# LoPoSwitchWiFi_v2_1.net
KiCad netlist of a schematic drawn in EasyEDA
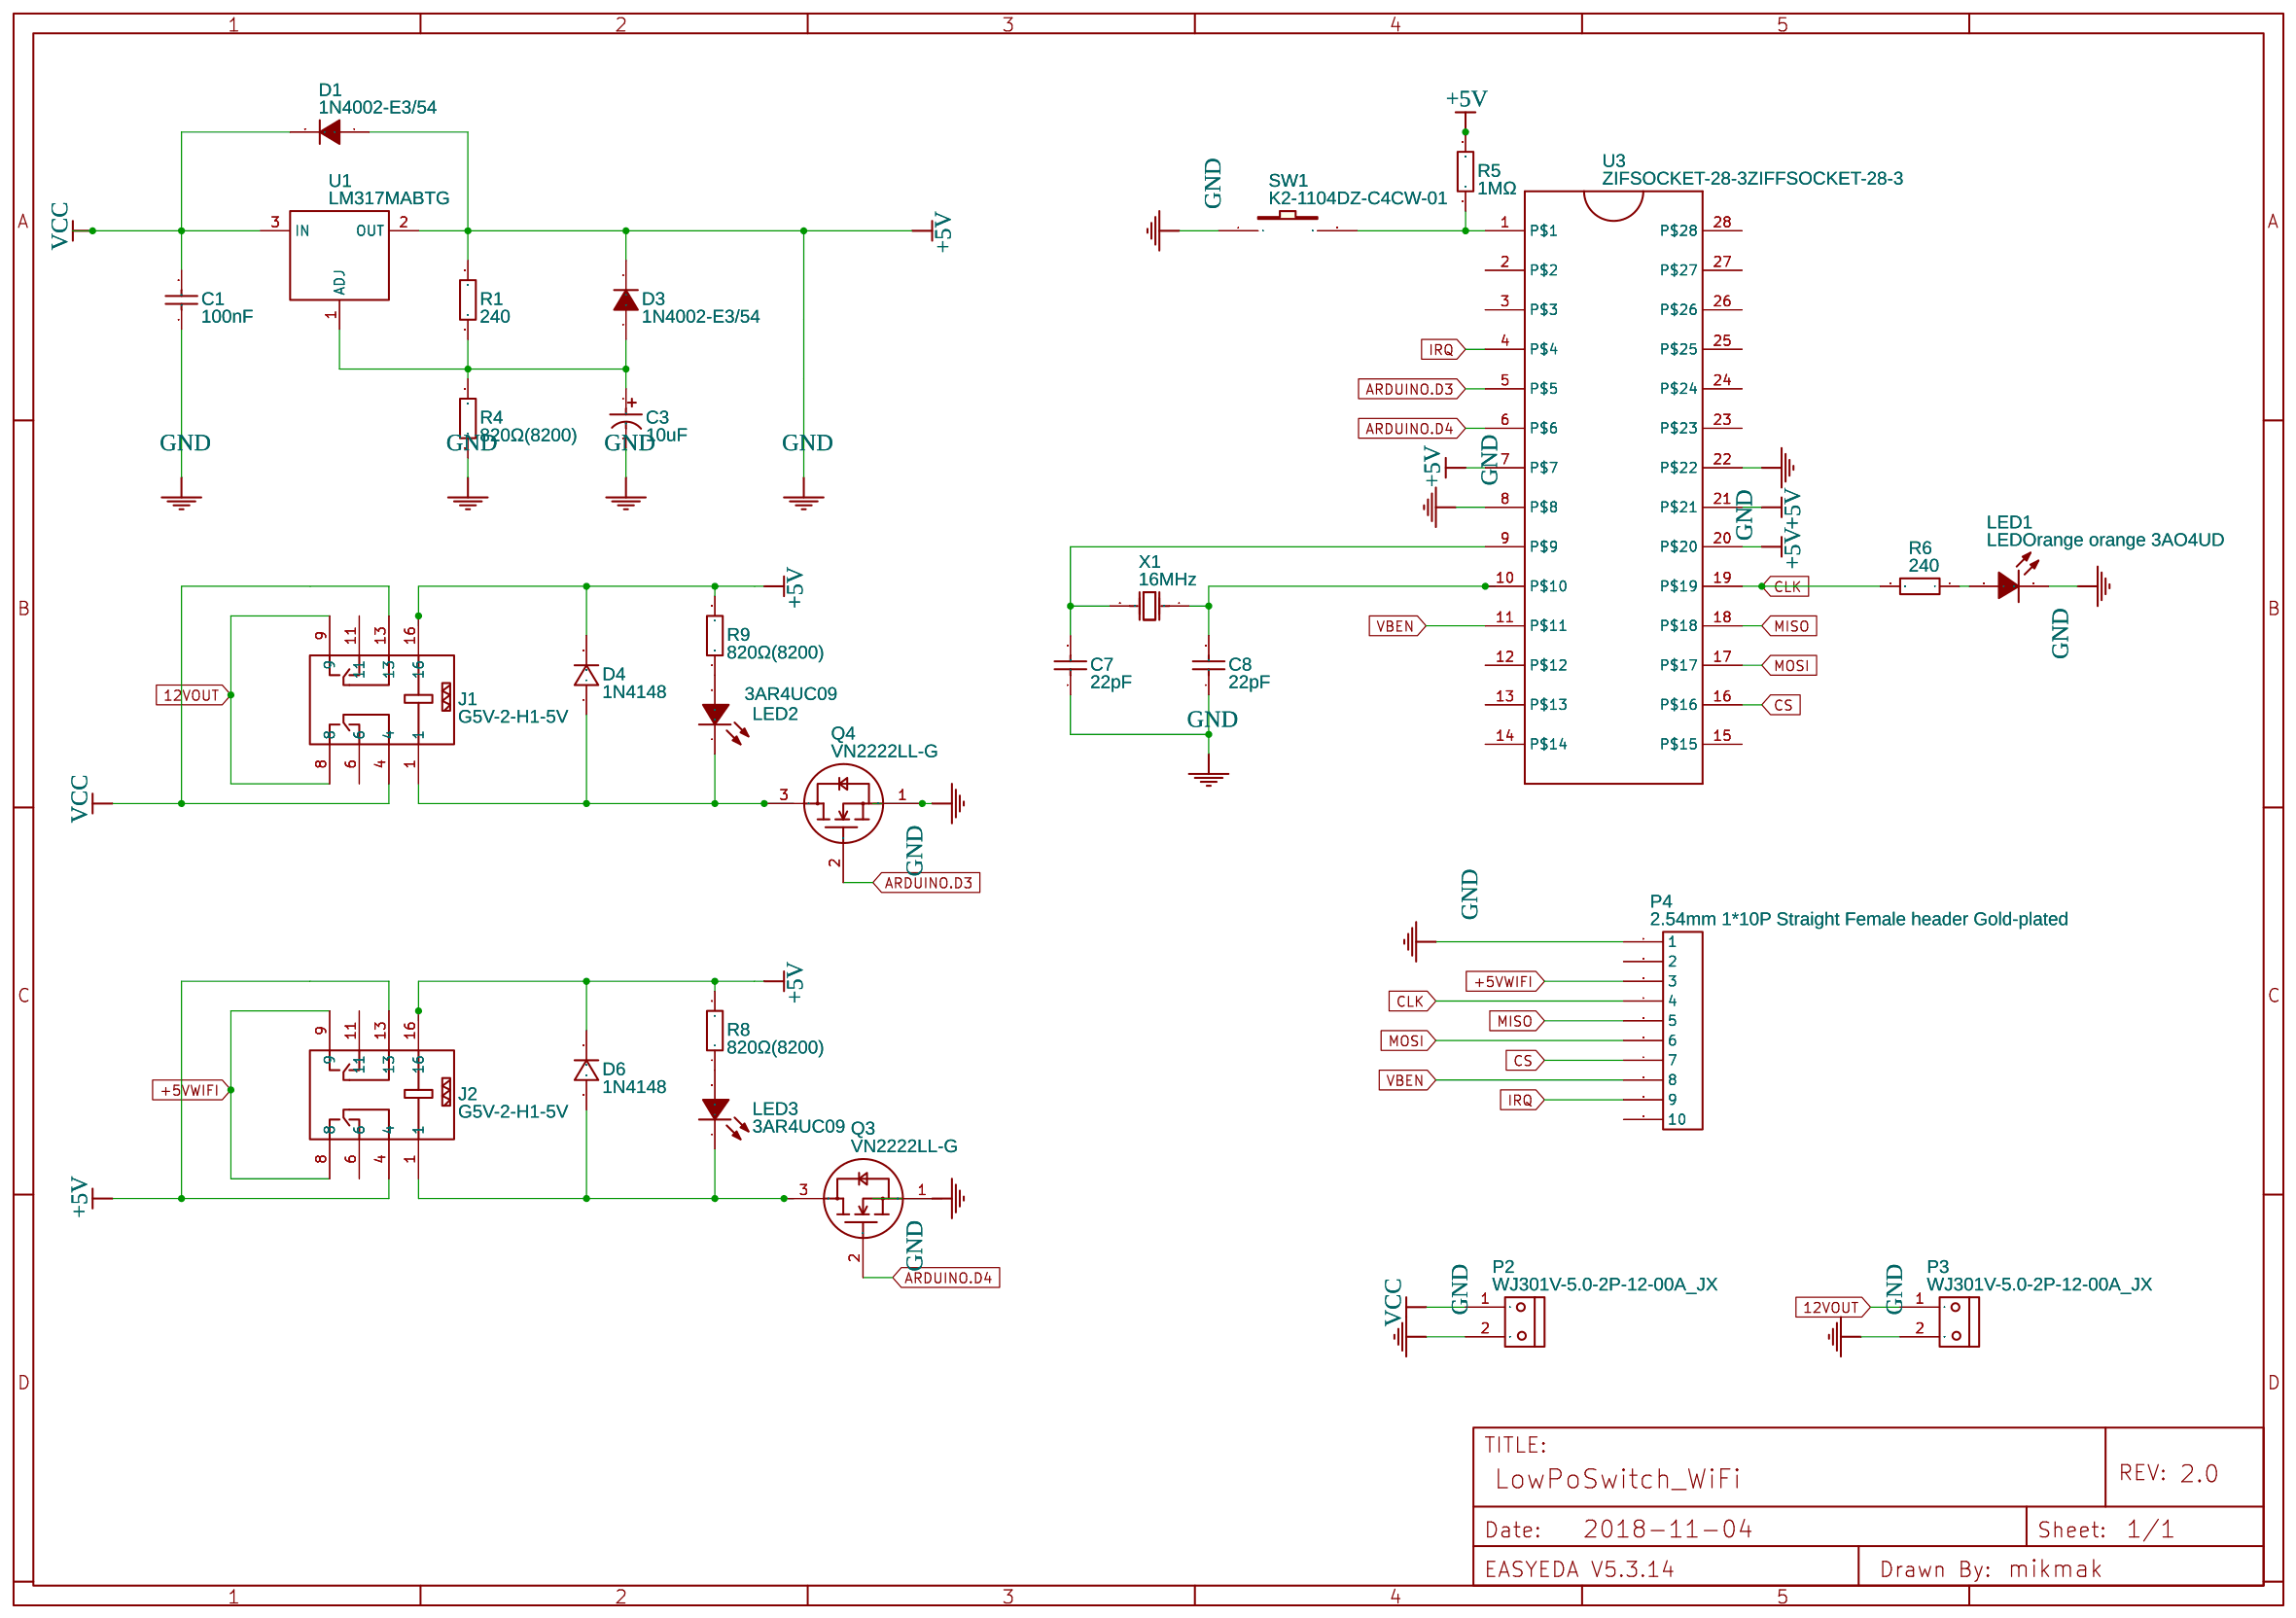
[diagram p0: schematic sheet]

(export (version "E")
  (design (tool "Eeschema 10.0.6"))
  (components
    (comp (ref "C1")
      (value "100nF")
      (fields
        (field (name "BOM_Manufacturer Part") "MPP104K5130508LC")
        (field (name "BOM_Supplier Part") "C109523")
      )
      (libsource (lib "") (part "MPP104K5130508LC"))
    )
    (comp (ref "C3")
      (value "10uF")
      (fields (field (name "BOM_Manufacturer Part") "10uf/100V") (field (name "BOM_Supplier Part") "C2029"))
      (libsource (lib "") (part "10uf/100V"))
    )
    (comp (ref "C7")
      (value "22pF")
      (fields
        (field (name "BOM_Manufacturer Part") "Monolithic0603N220J500")
        (field (name "BOM_Supplier Part") "C110283")
      )
      (libsource (lib "") (part "Monolithic0603N220J500"))
    )
    (comp (ref "C8")
      (value "22pF")
      (fields
        (field (name "BOM_Manufacturer Part") "Monolithic0603N220J500")
        (field (name "BOM_Supplier Part") "C110283")
      )
      (libsource (lib "") (part "Monolithic0603N220J500"))
    )
    (comp (ref "D1")
      (value "1N4002-E3/54")
      (fields (field (name "BOM_Supplier Part") "C33504"))
      (libsource (lib "") (part "Unknown_160_60"))
    )
    (comp (ref "D3")
      (value "1N4002-E3/54")
      (fields (field (name "BOM_Supplier Part") "C33504"))
      (libsource (lib "") (part "Unknown_310_145"))
    )
    (comp (ref "D4")
      (value "1N4148")
      (fields (field (name "BOM_Supplier Part") "C163750"))
      (libsource (lib "") (part "Unknown_290_335"))
    )
    (comp (ref "D6")
      (value "1N4148")
      (fields (field (name "BOM_Supplier Part") "C163750"))
      (libsource (lib "") (part "Unknown_290_535"))
    )
    (comp (ref "J1")
      (value "G5V-2-H1-5V")
      (fields (field (name "BOM_Supplier Part") "C28066"))
      (libsource (lib "") (part "Unknown_185_340"))
    )
    (comp (ref "J2")
      (value "G5V-2-H1-5V")
      (fields (field (name "BOM_Supplier Part") "C28066"))
      (libsource (lib "") (part "Unknown_185_540"))
    )
    (comp (ref "LED1")
      (value "LEDOrange orange 3AO4UD")
      (fields (field (name "BOM_Supplier Part") "C62095"))
      (libsource (lib "") (part "Unknown_1010_290"))
    )
    (comp (ref "LED2")
      (value "3AR4UC09")
      (fields (field (name "BOM_Supplier Part") "C6211"))
      (libsource (lib "") (part "Unknown_355_355"))
    )
    (comp (ref "LED3")
      (value "3AR4UC09")
      (fields (field (name "BOM_Supplier Part") "C6211"))
      (libsource (lib "") (part "Unknown_355_555"))
    )
    (comp (ref "P2")
      (value "WJ301V-5.0-2P-12-00A_JX")
      (fields (field (name "BOM_Manufacturer Part") "?") (field (name "BOM_Supplier Part") "C72326"))
      (libsource (lib "") (part "Unknown_755_655"))
    )
    (comp (ref "P3")
      (value "WJ301V-5.0-2P-12-00A_JX")
      (fields (field (name "BOM_Manufacturer Part") "?") (field (name "BOM_Supplier Part") "C72326"))
      (libsource (lib "") (part "Unknown_975_655"))
    )
    (comp (ref "P4")
      (value "2.54mm 1*10P Straight Female header Gold-plated")
      (fields (field (name "BOM_Supplier Part") "C35445"))
      (libsource (lib "") (part "Unknown_825_510"))
    )
    (comp (ref "Q3")
      (value "VN2222LL-G")
      (fields (field (name "BOM_Supplier Part") "C152170"))
      (libsource (lib "") (part "Unknown_430_610"))
    )
    (comp (ref "Q4")
      (value "VN2222LL-G")
      (fields (field (name "BOM_Supplier Part") "C152170"))
      (libsource (lib "") (part "Unknown_420_410"))
    )
    (comp (ref "R1")
      (value "240")
      (fields
        (field (name "BOM_Manufacturer Part") "MF1/8W-240Ω±1% T52")
        (field (name "BOM_Supplier Part") "C119165")
      )
      (libsource (lib "") (part "MF1/8W-240Ω±1% T52_1"))
    )
    (comp (ref "R4")
      (value "820Ω(8200)")
      (fields
        (field (name "BOM_Manufacturer Part") "MF1/8W-820Ω±1% T52")
        (field (name "BOM_Supplier Part") "C119177")
      )
      (libsource (lib "") (part "MF1/8W-820Ω±1% T52"))
    )
    (comp (ref "R5")
      (value "1MΩ")
      (fields
        (field (name "BOM_Manufacturer Part") "MFR0W4F1004A50")
        (field (name "BOM_Supplier Part") "C58596")
      )
      (libsource (lib "") (part "MFR0W4F1004A50"))
    )
    (comp (ref "R6")
      (value "240")
      (fields
        (field (name "BOM_Manufacturer Part") "MF1/8W-240Ω±1% T52")
        (field (name "BOM_Supplier Part") "C119165")
      )
      (libsource (lib "") (part "MF1/8W-240Ω±1% T52"))
    )
    (comp (ref "R8")
      (value "820Ω(8200)")
      (fields
        (field (name "BOM_Manufacturer Part") "MF1/8W-820Ω±1% T52")
        (field (name "BOM_Supplier Part") "C119177")
      )
      (libsource (lib "") (part "MF1/8W-820Ω±1% T52"))
    )
    (comp (ref "R9")
      (value "820Ω(8200)")
      (fields
        (field (name "BOM_Manufacturer Part") "MF1/8W-820Ω±1% T52")
        (field (name "BOM_Supplier Part") "C119177")
      )
      (libsource (lib "") (part "MF1/8W-820Ω±1% T52"))
    )
    (comp (ref "SW1")
      (value "K2-1104DZ-C4CW-01")
      (fields (field (name "BOM_Supplier Part") "C145889"))
      (libsource (lib "") (part "Unknown_640_110"))
    )
    (comp (ref "U1")
      (value "LM317MABTG")
      (fields (field (name "BOM_Supplier Part") "C94823"))
      (libsource (lib "") (part "Unknown_165_120"))
    )
    (comp (ref "U3")
      (value "ZIFSOCKET-28-3ZIFFSOCKET-28-3")
      (fields (field (name "BOM_Manufacturer Part") "?"))
      (libsource (lib "") (part "Unknown_765_390"))
    )
    (comp (ref "X1")
      (value "16MHz")
      (fields
        (field (name "BOM_Manufacturer Part") "X49SD16MSD2SC")
        (field (name "BOM_Supplier Part") "C16212")
      )
      (libsource (lib "") (part "X49SD16MSD2SC"))
    )
  )
  (nets
    (net (code "1") (name "+5V") (class "Default")
      (node (ref "C1") (pin "1") (pinfunction "1_1") (pintype "input"))
      (node (ref "C3") (pin "2") (pinfunction "2_2") (pintype "input"))
      (node (ref "C7") (pin "1") (pinfunction "1_1") (pintype "input"))
      (node (ref "C8") (pin "1") (pinfunction "1_1") (pintype "input"))
      (node (ref "D1") (pin "1") (pinfunction "A_1") (pintype "unspecified"))
      (node (ref "D3") (pin "2") (pinfunction "K_2") (pintype "unspecified"))
      (node (ref "D4") (pin "2") (pinfunction "2_2") (pintype "unspecified"))
      (node (ref "D6") (pin "2") (pinfunction "2_2") (pintype "unspecified"))
      (node (ref "J1") (pin "16") (pinfunction "16_16") (pintype "unspecified"))
      (node (ref "J2") (pin "13") (pinfunction "13_13") (pintype "unspecified"))
      (node (ref "J2") (pin "16") (pinfunction "16_16") (pintype "unspecified"))
      (node (ref "J2") (pin "4") (pinfunction "4_4") (pintype "unspecified"))
      (node (ref "LED1") (pin "1") (pinfunction "K_1") (pintype "unspecified"))
      (node (ref "P2") (pin "2") (pinfunction "2_2") (pintype "unspecified"))
      (node (ref "P3") (pin "2") (pinfunction "2_2") (pintype "unspecified"))
      (node (ref "P4") (pin "1") (pinfunction "1_1") (pintype "input"))
      (node (ref "Q4") (pin "1") (pinfunction "S_1") (pintype "unspecified"))
      (node (ref "R1") (pin "2") (pinfunction "2_2") (pintype "input"))
      (node (ref "R4") (pin "1") (pinfunction "1_1") (pintype "input"))
      (node (ref "R5") (pin "2") (pinfunction "2_2") (pintype "input"))
      (node (ref "R8") (pin "2") (pinfunction "2_2") (pintype "input"))
      (node (ref "R9") (pin "2") (pinfunction "2_2") (pintype "input"))
      (node (ref "SW1") (pin "1") (pinfunction "1_1") (pintype "input"))
      (node (ref "U1") (pin "2") (pinfunction "OUT_2") (pintype "unspecified"))
      (node (ref "U3") (pin "20") (pinfunction "P$20_20") (pintype "unspecified"))
      (node (ref "U3") (pin "21") (pinfunction "P$21_21") (pintype "unspecified"))
      (node (ref "U3") (pin "22") (pinfunction "P$22_22") (pintype "unspecified"))
      (node (ref "U3") (pin "7") (pinfunction "P$7_7") (pintype "unspecified"))
      (node (ref "U3") (pin "8") (pinfunction "P$8_8") (pintype "unspecified"))
    )
    (net (code "2") (name "+5VWIFI") (class "Default")
      (node (ref "J2") (pin "8") (pinfunction "8_8") (pintype "unspecified"))
      (node (ref "J2") (pin "9") (pinfunction "9_9") (pintype "unspecified"))
      (node (ref "P4") (pin "3") (pinfunction "3_3") (pintype "input"))
    )
    (net (code "3") (name "12VOUT") (class "Default")
      (node (ref "J1") (pin "8") (pinfunction "8_8") (pintype "unspecified"))
      (node (ref "J1") (pin "9") (pinfunction "9_9") (pintype "unspecified"))
      (node (ref "P3") (pin "1") (pinfunction "1_1") (pintype "unspecified"))
    )
    (net (code "4") (name "ARDUINO.D3") (class "Default")
      (node (ref "Q4") (pin "2") (pinfunction "G_2") (pintype "unspecified"))
      (node (ref "U3") (pin "5") (pinfunction "P$5_5") (pintype "unspecified"))
    )
    (net (code "5") (name "ARDUINO.D4") (class "Default")
      (node (ref "Q3") (pin "2") (pinfunction "G_2") (pintype "unspecified"))
      (node (ref "U3") (pin "6") (pinfunction "P$6_6") (pintype "unspecified"))
    )
    (net (code "6") (name "CLK") (class "Default")
      (node (ref "P4") (pin "4") (pinfunction "4_4") (pintype "input"))
      (node (ref "R6") (pin "2") (pinfunction "2_2") (pintype "input"))
      (node (ref "U3") (pin "19") (pinfunction "P$19_19") (pintype "unspecified"))
    )
    (net (code "7") (name "CS") (class "Default")
      (node (ref "P4") (pin "7") (pinfunction "7_7") (pintype "input"))
      (node (ref "U3") (pin "16") (pinfunction "P$16_16") (pintype "unspecified"))
    )
    (net (code "8") (name "IRQ") (class "Default")
      (node (ref "P4") (pin "9") (pinfunction "9_9") (pintype "input"))
      (node (ref "U3") (pin "4") (pinfunction "P$4_4") (pintype "unspecified"))
    )
    (net (code "9") (name "MISO") (class "Default")
      (node (ref "P4") (pin "5") (pinfunction "5_5") (pintype "input"))
      (node (ref "U3") (pin "18") (pinfunction "P$18_18") (pintype "unspecified"))
    )
    (net (code "10") (name "MOSI") (class "Default")
      (node (ref "P4") (pin "6") (pinfunction "6_6") (pintype "input"))
      (node (ref "U3") (pin "17") (pinfunction "P$17_17") (pintype "unspecified"))
    )
    (net (code "11") (name "Net-(D3-A)") (class "Default")
      (node (ref "C3") (pin "1") (pinfunction "1_1") (pintype "input"))
      (node (ref "D3") (pin "1") (pinfunction "A_1") (pintype "unspecified"))
      (node (ref "R1") (pin "1") (pinfunction "1_1") (pintype "input"))
      (node (ref "R4") (pin "2") (pinfunction "2_2") (pintype "input"))
      (node (ref "U1") (pin "1") (pinfunction "ADJ_1") (pintype "input"))
    )
    (net (code "12") (name "Net-(LED1-A)") (class "Default")
      (node (ref "LED1") (pin "2") (pinfunction "A_2") (pintype "unspecified"))
      (node (ref "R6") (pin "1") (pinfunction "1_1") (pintype "input"))
    )
    (net (code "13") (name "Net-(LED2-A)") (class "Default")
      (node (ref "LED2") (pin "2") (pinfunction "A_2") (pintype "unspecified"))
      (node (ref "R9") (pin "1") (pinfunction "1_1") (pintype "input"))
    )
    (net (code "14") (name "Net-(LED2-K)") (class "Default")
      (node (ref "D4") (pin "1") (pinfunction "1_1") (pintype "unspecified"))
      (node (ref "J1") (pin "1") (pinfunction "1_1") (pintype "unspecified"))
      (node (ref "LED2") (pin "1") (pinfunction "K_1") (pintype "unspecified"))
      (node (ref "Q4") (pin "3") (pinfunction "D_3") (pintype "unspecified"))
    )
    (net (code "15") (name "Net-(LED3-A)") (class "Default")
      (node (ref "LED3") (pin "2") (pinfunction "A_2") (pintype "unspecified"))
      (node (ref "R8") (pin "1") (pinfunction "1_1") (pintype "input"))
    )
    (net (code "16") (name "Net-(LED3-K)") (class "Default")
      (node (ref "D6") (pin "1") (pinfunction "1_1") (pintype "unspecified"))
      (node (ref "J2") (pin "1") (pinfunction "1_1") (pintype "unspecified"))
      (node (ref "LED3") (pin "1") (pinfunction "K_1") (pintype "unspecified"))
      (node (ref "Q3") (pin "3") (pinfunction "D_3") (pintype "unspecified"))
    )
    (net (code "17") (name "Net-(U3-P$1)") (class "Default")
      (node (ref "R5") (pin "1") (pinfunction "1_1") (pintype "input"))
      (node (ref "SW1") (pin "2") (pinfunction "2_2") (pintype "input"))
      (node (ref "U3") (pin "1") (pinfunction "P$1_1") (pintype "unspecified"))
    )
    (net (code "18") (name "Net-(U3-P$9)") (class "Default")
      (node (ref "C7") (pin "2") (pinfunction "2_2") (pintype "input"))
      (node (ref "U3") (pin "9") (pinfunction "P$9_9") (pintype "unspecified"))
      (node (ref "X1") (pin "2") (pinfunction "OSC2_2") (pintype "input"))
    )
    (net (code "19") (name "Net-(U3-P$10)") (class "Default")
      (node (ref "C8") (pin "2") (pinfunction "2_2") (pintype "input"))
      (node (ref "U3") (pin "10") (pinfunction "P$10_10") (pintype "unspecified"))
      (node (ref "X1") (pin "1") (pinfunction "OSC1_1") (pintype "input"))
    )
    (net (code "20") (name "VBEN") (class "Default")
      (node (ref "P4") (pin "8") (pinfunction "8_8") (pintype "input"))
      (node (ref "U3") (pin "11") (pinfunction "P$11_11") (pintype "unspecified"))
    )
    (net (code "21") (name "VCC") (class "Default")
      (node (ref "C1") (pin "2") (pinfunction "2_2") (pintype "input"))
      (node (ref "D1") (pin "2") (pinfunction "K_2") (pintype "unspecified"))
      (node (ref "J1") (pin "13") (pinfunction "13_13") (pintype "unspecified"))
      (node (ref "J1") (pin "4") (pinfunction "4_4") (pintype "unspecified"))
      (node (ref "P2") (pin "1") (pinfunction "1_1") (pintype "unspecified"))
      (node (ref "U1") (pin "3") (pinfunction "IN_3") (pintype "input"))
    )
    (net (code "22") (name "unconnected-(J1-Pad6)") (class "Default")
      (node (ref "J1") (pin "6") (pinfunction "6_6") (pintype "unspecified"))
    )
    (net (code "23") (name "unconnected-(J1-Pad11)") (class "Default")
      (node (ref "J1") (pin "11") (pinfunction "11_11") (pintype "unspecified"))
    )
    (net (code "24") (name "unconnected-(J2-Pad6)") (class "Default")
      (node (ref "J2") (pin "6") (pinfunction "6_6") (pintype "unspecified"))
    )
    (net (code "25") (name "unconnected-(J2-Pad11)") (class "Default")
      (node (ref "J2") (pin "11") (pinfunction "11_11") (pintype "unspecified"))
    )
    (net (code "26") (name "unconnected-(P4-Pad2)") (class "Default")
      (node (ref "P4") (pin "2") (pinfunction "2_2") (pintype "input"))
    )
    (net (code "27") (name "unconnected-(P4-Pad10)") (class "Default")
      (node (ref "P4") (pin "10") (pinfunction "10_10") (pintype "input"))
    )
    (net (code "28") (name "unconnected-(Q3-S-Pad1)") (class "Default")
      (node (ref "Q3") (pin "1") (pinfunction "S_1") (pintype "unspecified"))
    )
    (net (code "29") (name "unconnected-(U3-P$2-Pad2)") (class "Default")
      (node (ref "U3") (pin "2") (pinfunction "P$2_2") (pintype "unspecified"))
    )
    (net (code "30") (name "unconnected-(U3-P$3-Pad3)") (class "Default")
      (node (ref "U3") (pin "3") (pinfunction "P$3_3") (pintype "unspecified"))
    )
    (net (code "31") (name "unconnected-(U3-P$12-Pad12)") (class "Default")
      (node (ref "U3") (pin "12") (pinfunction "P$12_12") (pintype "unspecified"))
    )
    (net (code "32") (name "unconnected-(U3-P$13-Pad13)") (class "Default")
      (node (ref "U3") (pin "13") (pinfunction "P$13_13") (pintype "unspecified"))
    )
    (net (code "33") (name "unconnected-(U3-P$14-Pad14)") (class "Default")
      (node (ref "U3") (pin "14") (pinfunction "P$14_14") (pintype "unspecified"))
    )
    (net (code "34") (name "unconnected-(U3-P$15-Pad15)") (class "Default")
      (node (ref "U3") (pin "15") (pinfunction "P$15_15") (pintype "unspecified"))
    )
    (net (code "35") (name "unconnected-(U3-P$23-Pad23)") (class "Default")
      (node (ref "U3") (pin "23") (pinfunction "P$23_23") (pintype "unspecified"))
    )
    (net (code "36") (name "unconnected-(U3-P$24-Pad24)") (class "Default")
      (node (ref "U3") (pin "24") (pinfunction "P$24_24") (pintype "unspecified"))
    )
    (net (code "37") (name "unconnected-(U3-P$25-Pad25)") (class "Default")
      (node (ref "U3") (pin "25") (pinfunction "P$25_25") (pintype "unspecified"))
    )
    (net (code "38") (name "unconnected-(U3-P$26-Pad26)") (class "Default")
      (node (ref "U3") (pin "26") (pinfunction "P$26_26") (pintype "unspecified"))
    )
    (net (code "39") (name "unconnected-(U3-P$27-Pad27)") (class "Default")
      (node (ref "U3") (pin "27") (pinfunction "P$27_27") (pintype "unspecified"))
    )
    (net (code "40") (name "unconnected-(U3-P$28-Pad28)") (class "Default")
      (node (ref "U3") (pin "28") (pinfunction "P$28_28") (pintype "unspecified"))
    )
  )
)
